# Power_Regulation.net
KiCad netlist of a schematic drawn in Altium Designer
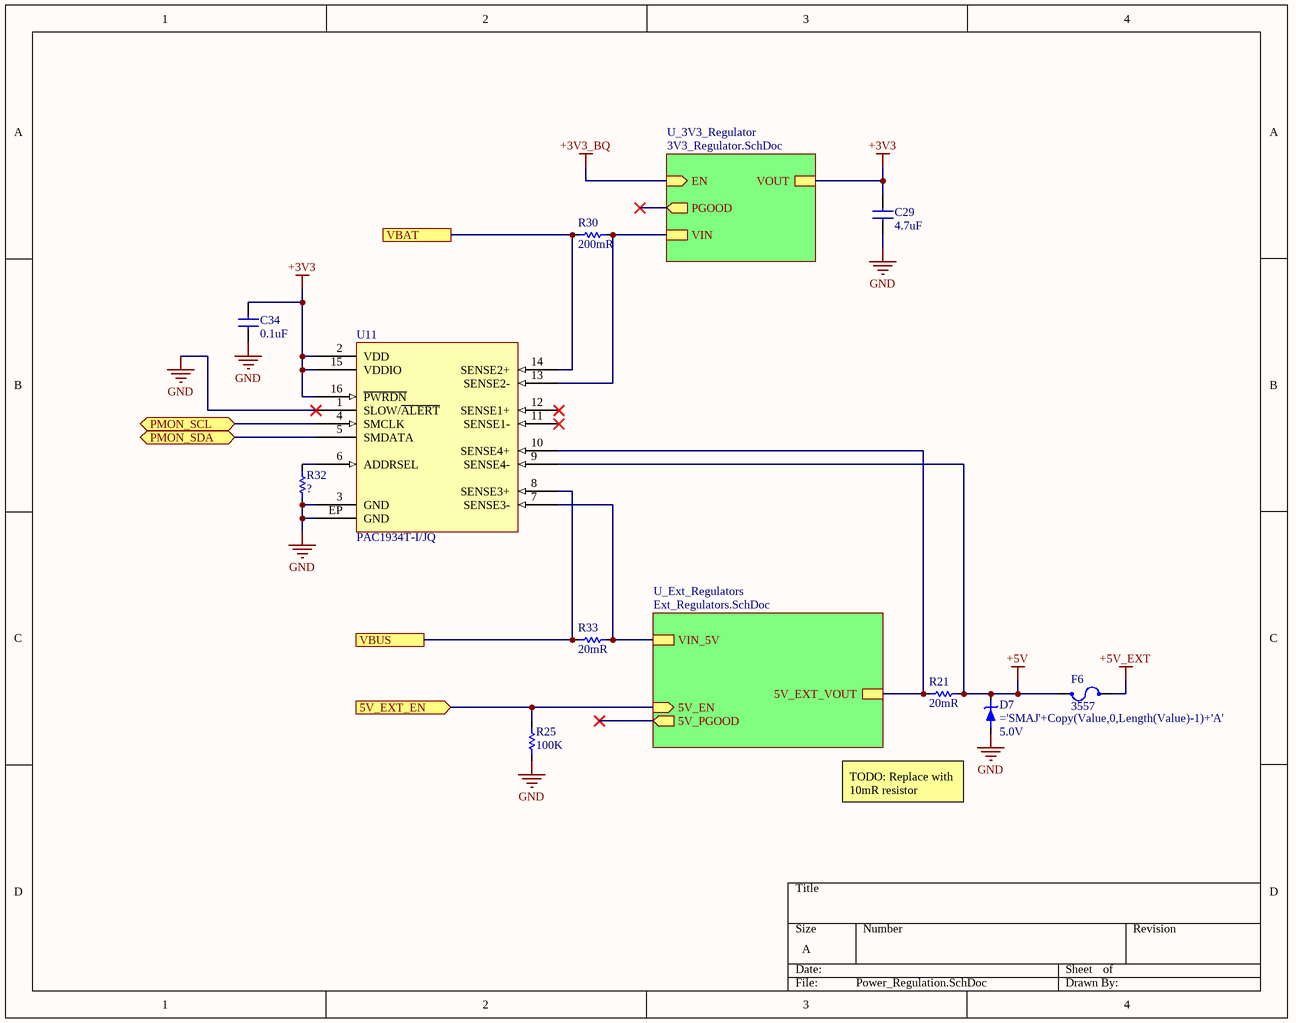
[diagram p0: Power_Regulation.SchDoc]

(export (version "E")
  (design (tool "Eeschema 10.0.6"))
  (components
    (comp (ref "C29")
      (value "4.7uF")
      (footprint "0805_Capacitor")
      (description "CAP CERM 4.7uF 10% 16V 0805")
      (fields
        (field (name "VOLTAGE") "16V")
        (field (name "Comment") "CAP 4.7uF 16V X5R")
        (field (name "SVP CREATOR") "Spencer Berglund")
      )
      (libsource (lib "capacitor") (part "C_0805_4.7uF_16V_10%"))
    )
    (comp (ref "C34")
      (value "0.1uF")
      (footprint "0402_CAPACITOR")
      (description "CAP CERM 0.1uF 10% 16V 0402")
      (fields (field (name "VOLTAGE") "16V") (field (name "Comment") "CAP 0.1uF 16V X7R"))
      (libsource (lib "capacitor") (part "C_0402_0.1uF_16V_10%"))
    )
    (comp (ref "D7")
      (value "5.0V")
      (footprint "SMA")
      (description "SMA Unidirectional TVS Diode")
      (fields
        (field (name "MANUFACTURER") "Vishay")
        (field (name "MANUFACTURER PN") "SMAJA")
        (field (name "Comment") "TVS Diode")
      )
      (libsource (lib "diode") (part "D_TVS_SMAJ_Uni_generic"))
    )
    (comp (ref "F6")
      (value "3557")
      (footprint "F_3557_Mini")
      (fields (field (name "MANUFACTURER") "Keystone Electronics") (field (name "VOLTAGE") "500V"))
      (libsource (lib "misc") (part "F_3557_MINI_ATO"))
    )
    (comp (ref "R21")
      (value "20mR")
      (footprint "0805_Resistor")
      (fields
        (field (name "MANUFACTURER") "Bourns")
        (field (name "MANUFACTURER PART NUMBER") "CRF0805-FZ-R020ELF")
        (field (name "TOLERANCE") "1%")
      )
      (libsource (lib "resistor") (part "R_CRF0805-FZ-R020ELF"))
    )
    (comp (ref "R25")
      (value "100K")
      (footprint "0402_Resistor")
      (description "Generic 0402 Resistor (10.2R to 10M)")
      (fields (field (name "TOLERANCE") "±1%") (field (name "MANUFACTURER") "Yageo"))
      (libsource (lib "resistor") (part "R_0402_generic_1%"))
    )
    (comp (ref "R30")
      (value "200mR")
      (footprint "0603_Resistor")
      (description "200 mOhms ±1% 0.125W, 1/8W Chip Resistor 0603 (1608 Metric) Current Sense Thick Film")
      (fields
        (field (name "MANUFACTURER") "Stackpole Electronics")
        (field (name "MANUFACTURER PART NUMBER") "CSR0603FKR200")
      )
      (libsource (lib "resistor") (part "R_CSR0603FKR200"))
    )
    (comp (ref "R32")
      (value "?")
      (footprint "0402_Resistor")
      (description "Generic 0402 Resistor (10.2R to 10M)")
      (fields (field (name "TOLERANCE") "±1%") (field (name "MANUFACTURER") "Yageo"))
      (libsource (lib "resistor") (part "R_0402_generic_1%"))
    )
    (comp (ref "R33")
      (value "20mR")
      (footprint "0805_Resistor")
      (fields
        (field (name "MANUFACTURER") "Bourns")
        (field (name "MANUFACTURER PART NUMBER") "CRF0805-FZ-R020ELF")
        (field (name "TOLERANCE") "1%")
      )
      (libsource (lib "resistor") (part "R_CRF0805-FZ-R020ELF"))
    )
    (comp (ref "U11")
      (value "PAC1934T-I/JQ")
      (footprint "QFN-16-EP_4x4mm")
      (description "Current Monitor Regulator High-Side 16-UQFN (4x4)")
      (libsource (lib "ic") (part "U_PAC1934T-I/JQ"))
    )
  )
  (nets
    (net (code "1") (name "+3V3") (class "Default")
      (node (ref "C29") (pin "1") (pinfunction "1_1") (pintype "passive"))
      (node (ref "C34") (pin "1") (pinfunction "1_1") (pintype "passive"))
      (node (ref "U11") (pin "15") (pinfunction "VDDIO_15") (pintype "power_in"))
      (node (ref "U11") (pin "16") (pinfunction "~{PWRDN}_16") (pintype "input"))
      (node (ref "U11") (pin "2") (pinfunction "VDD_2") (pintype "power_in"))
    )
    (net (code "3") (name "+5V") (class "Default")
      (node (ref "D7") (pin "2") (pinfunction "Cathode_2") (pintype "passive"))
      (node (ref "F6") (pin "1") (pinfunction "1_1") (pintype "passive"))
      (node (ref "R21") (pin "2") (pinfunction "2_2") (pintype "passive"))
      (node (ref "U11") (pin "9") (pinfunction "SENSE4-_9") (pintype "input"))
    )
    (net (code "4") (name "+5V_EXT") (class "Default")
      (node (ref "F6") (pin "2") (pinfunction "2_2") (pintype "passive"))
    )
    (net (code "5") (name "/5V_EXT_EN") (class "Default")
      (node (ref "R25") (pin "2") (pinfunction "2_2") (pintype "passive"))
    )
    (net (code "6") (name "/5V_EXT_VOUT") (class "Default")
      (node (ref "R21") (pin "1") (pinfunction "1_1") (pintype "passive"))
      (node (ref "U11") (pin "10") (pinfunction "SENSE4+_10") (pintype "input"))
    )
    (net (code "9") (name "/PMON_SCL") (class "Default")
      (node (ref "U11") (pin "4") (pinfunction "SMCLK_4") (pintype "input"))
    )
    (net (code "10") (name "/PMON_SDA") (class "Default")
      (node (ref "U11") (pin "5") (pinfunction "SMDATA_5") (pintype "open_collector"))
    )
    (net (code "11") (name "/VBAT") (class "Default")
      (node (ref "R30") (pin "1") (pinfunction "1_1") (pintype "passive"))
      (node (ref "U11") (pin "14") (pinfunction "SENSE2+_14") (pintype "input"))
    )
    (net (code "12") (name "/VBUS") (class "Default")
      (node (ref "R33") (pin "1") (pinfunction "1_1") (pintype "passive"))
      (node (ref "U11") (pin "8") (pinfunction "SENSE3+_8") (pintype "input"))
    )
    (net (code "13") (name "/VIN") (class "Default")
      (node (ref "R30") (pin "2") (pinfunction "2_2") (pintype "passive"))
      (node (ref "U11") (pin "13") (pinfunction "SENSE2-_13") (pintype "input"))
    )
    (net (code "14") (name "/VIN_5V") (class "Default")
      (node (ref "R33") (pin "2") (pinfunction "2_2") (pintype "passive"))
      (node (ref "U11") (pin "7") (pinfunction "SENSE3-_7") (pintype "input"))
    )
    (net (code "15") (name "GND") (class "Default")
      (node (ref "C29") (pin "2") (pinfunction "2_2") (pintype "passive"))
      (node (ref "C34") (pin "2") (pinfunction "2_2") (pintype "passive"))
      (node (ref "D7") (pin "1") (pinfunction "Anode_1") (pintype "passive"))
      (node (ref "R25") (pin "1") (pinfunction "1_1") (pintype "passive"))
      (node (ref "R32") (pin "1") (pinfunction "1_1") (pintype "passive"))
      (node (ref "U11") (pin "1") (pinfunction "SLOW/~{ALERT}_1") (pintype "open_collector"))
      (node (ref "U11") (pin "3") (pinfunction "GND_3") (pintype "power_in"))
      (node (ref "U11") (pin "EP") (pinfunction "GND_EP") (pintype "passive"))
    )
    (net (code "16") (name "Net-(U11-ADDRSEL)") (class "Default")
      (node (ref "R32") (pin "2") (pinfunction "2_2") (pintype "passive"))
      (node (ref "U11") (pin "6") (pinfunction "ADDRSEL_6") (pintype "input"))
    )
    (net (code "17") (name "unconnected-(U11-SENSE1+-Pad12)") (class "Default")
      (node (ref "U11") (pin "12") (pinfunction "SENSE1+_12") (pintype "input+no_connect"))
    )
    (net (code "18") (name "unconnected-(U11-SENSE1--Pad11)") (class "Default")
      (node (ref "U11") (pin "11") (pinfunction "SENSE1-_11") (pintype "input+no_connect"))
    )
  )
)
